# sgd710_pic32_sch.net
KiCad netlist of a schematic drawn in EAGLE
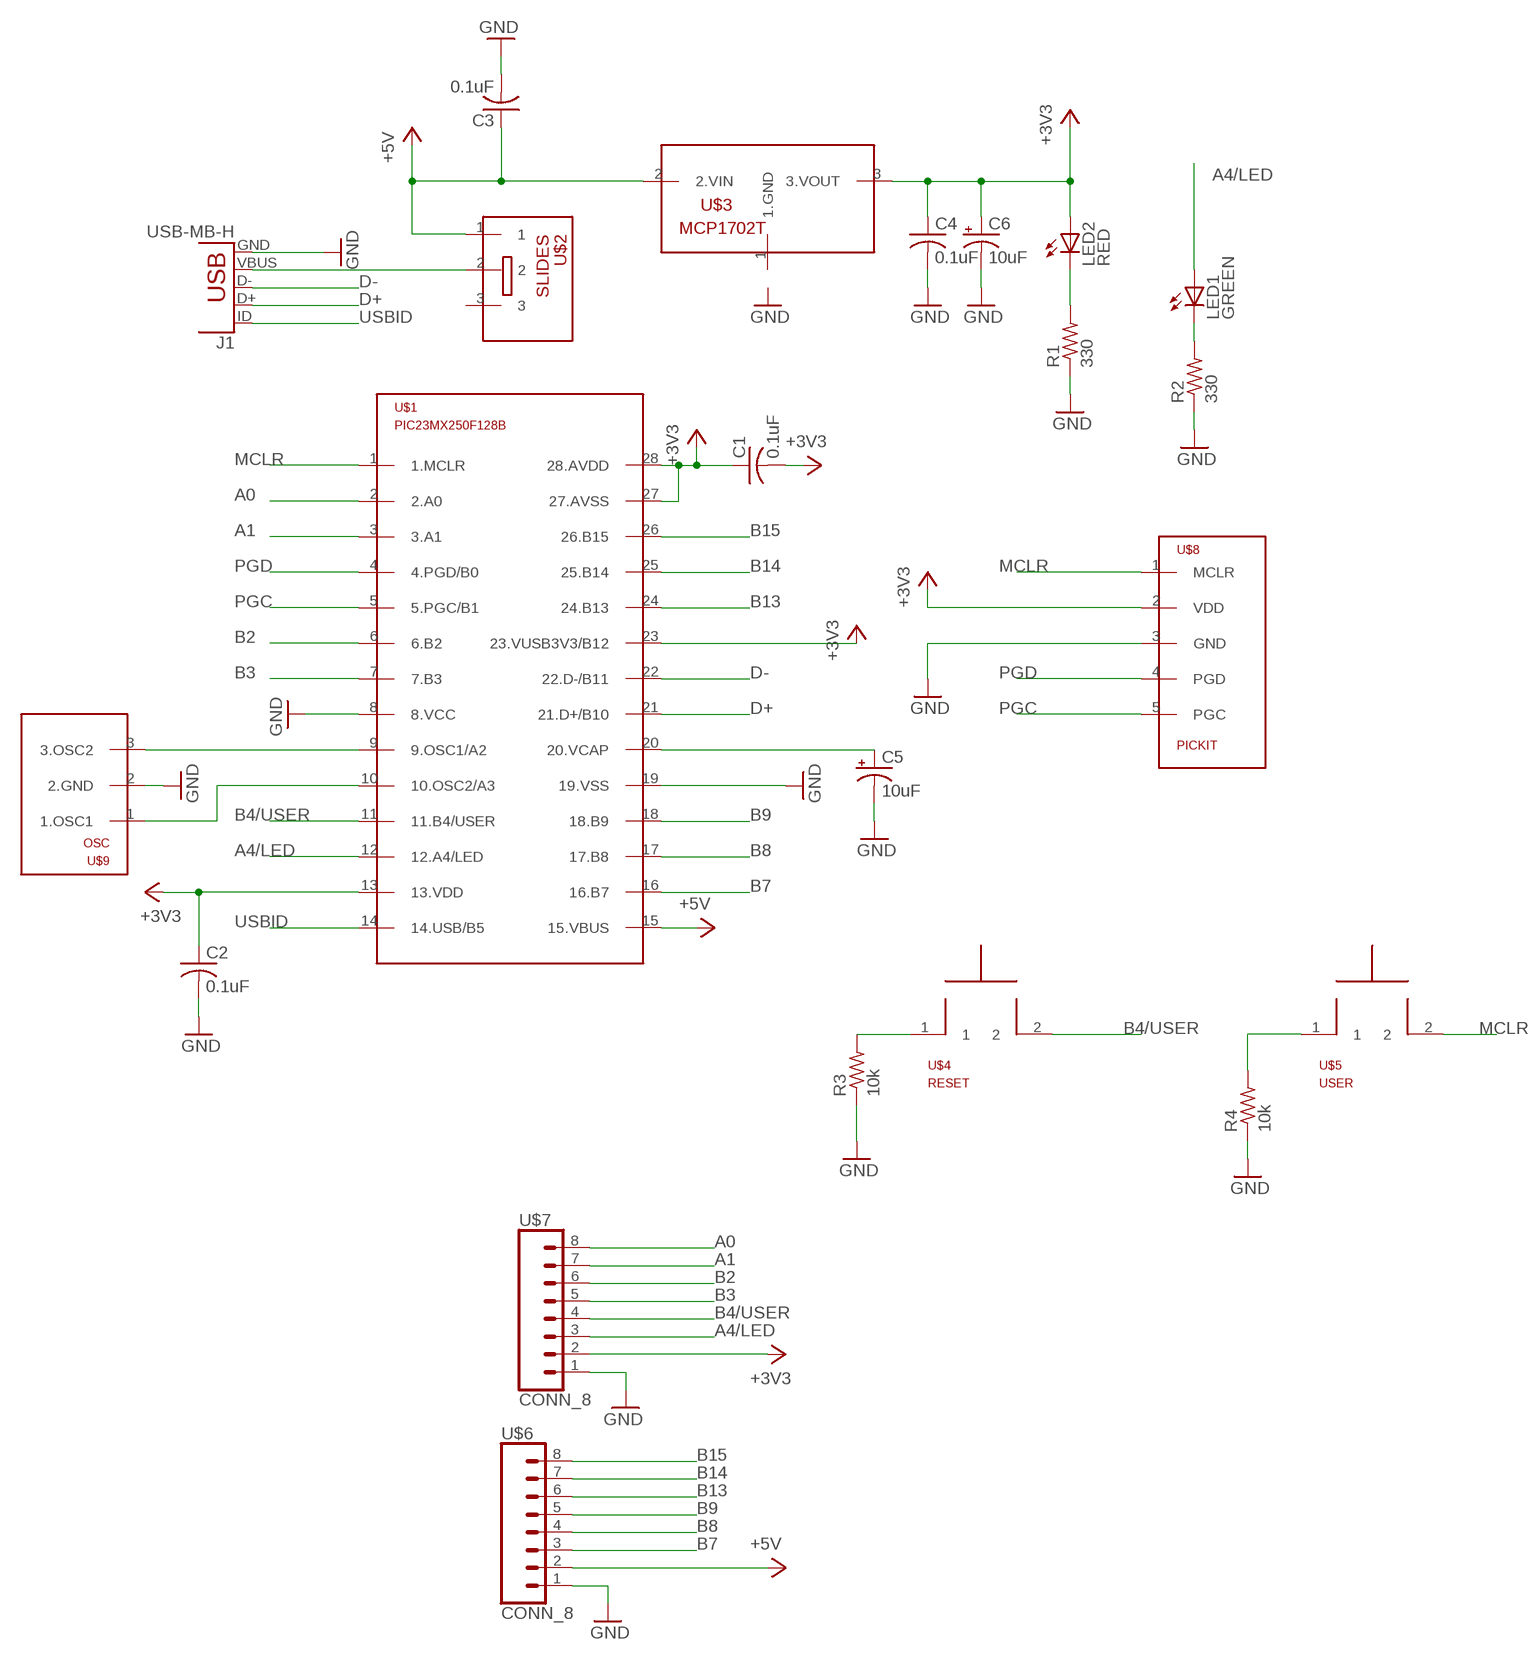
[diagram p0: schematic, sheet 1]

(export (version "E")
  (design (tool "Eeschema 10.0.6"))
  (components
    (comp (ref "C1")
      (value "0.1uF")
      (footprint "eagle-import:C025-025X050")
      (libsource (lib "eagle-import") (part "C-US025-025X050"))
    )
    (comp (ref "C2")
      (value "0.1uF")
      (footprint "eagle-import:C025-025X050")
      (libsource (lib "eagle-import") (part "C-US025-025X050"))
    )
    (comp (ref "C3")
      (value "0.1uF")
      (footprint "eagle-import:C025-025X050")
      (libsource (lib "eagle-import") (part "C-US025-025X050"))
    )
    (comp (ref "C4")
      (value "0.1uF")
      (footprint "eagle-import:C025-025X050")
      (libsource (lib "eagle-import") (part "C-US025-025X050"))
    )
    (comp (ref "C5")
      (value "10uF")
      (footprint "eagle-import:B45181A")
      (libsource (lib "eagle-import") (part "CPOL-USB45181A"))
    )
    (comp (ref "C6")
      (value "10uF")
      (footprint "eagle-import:B45181A")
      (libsource (lib "eagle-import") (part "CPOL-USB45181A"))
    )
    (comp (ref "J1")
      (value "USB-MB-H")
      (footprint "eagle-import:USB-MB-H")
      (libsource (lib "eagle-import") (part "USB-MB-H"))
    )
    (comp (ref "LED1")
      (value "GREEN")
      (footprint "eagle-import:LED3MM")
      (libsource (lib "eagle-import") (part "LED3MM"))
    )
    (comp (ref "LED2")
      (value "RED")
      (footprint "eagle-import:LED3MM")
      (libsource (lib "eagle-import") (part "LED3MM"))
    )
    (comp (ref "R1")
      (value "330")
      (footprint "eagle-import:0207_10")
      (libsource (lib "eagle-import") (part "R-US_0207/10"))
    )
    (comp (ref "R2")
      (value "330")
      (footprint "eagle-import:0207_10")
      (libsource (lib "eagle-import") (part "R-US_0207/10"))
    )
    (comp (ref "R3")
      (value "10k")
      (footprint "eagle-import:0207_10")
      (libsource (lib "eagle-import") (part "R-US_0207/10"))
    )
    (comp (ref "R4")
      (value "10k")
      (footprint "eagle-import:0207_10")
      (libsource (lib "eagle-import") (part "R-US_0207/10"))
    )
    (comp (ref "U$1")
      (value "PIC23MX250F128B")
      (footprint "eagle-import:DIL28-3")
      (libsource (lib "eagle-import") (part "PIC23MX250F128B"))
    )
    (comp (ref "U$2")
      (value "SLIDES")
      (footprint "eagle-import:SLIDE")
      (libsource (lib "eagle-import") (part "SLIDES"))
    )
    (comp (ref "U$3")
      (value "MCP1702T")
      (footprint "eagle-import:TO92")
      (libsource (lib "eagle-import") (part "MCP1702T"))
    )
    (comp (ref "U$4")
      (value "RESET")
      (footprint "eagle-import:PB")
      (libsource (lib "eagle-import") (part "PB"))
    )
    (comp (ref "U$5")
      (value "USER")
      (footprint "eagle-import:PB")
      (libsource (lib "eagle-import") (part "PB"))
    )
    (comp (ref "U$6")
      (value "CONN_8")
      (footprint "eagle-import:1X08")
      (libsource (lib "eagle-import") (part "CONN_8"))
    )
    (comp (ref "U$7")
      (value "CONN_8")
      (footprint "eagle-import:1X08")
      (libsource (lib "eagle-import") (part "CONN_8"))
    )
    (comp (ref "U$8")
      (value "PICKIT")
      (footprint "eagle-import:1X05")
      (libsource (lib "eagle-import") (part "PICKIT"))
    )
    (comp (ref "U$9")
      (value "OSC")
      (footprint "eagle-import:OSC")
      (libsource (lib "eagle-import") (part "OSC"))
    )
  )
  (nets
    (net (code "1") (name "+3V3") (class "Default")
      (node (ref "C1") (pin "1") (pinfunction "1_1") (pintype "passive"))
      (node (ref "C1") (pin "2") (pinfunction "2_2") (pintype "passive"))
      (node (ref "C2") (pin "1") (pinfunction "1_1") (pintype "passive"))
      (node (ref "C4") (pin "1") (pinfunction "1_1") (pintype "passive"))
      (node (ref "C6") (pin "+") (pinfunction "+_+") (pintype "passive"))
      (node (ref "LED2") (pin "A") (pinfunction "A_A") (pintype "passive"))
      (node (ref "U$1") (pin "13") (pinfunction "13.VDD_13") (pintype "bidirectional"))
      (node (ref "U$1") (pin "23") (pinfunction "23.VUSB3V3/B12_23") (pintype "bidirectional"))
      (node (ref "U$1") (pin "27") (pinfunction "27.AVSS_27") (pintype "bidirectional"))
      (node (ref "U$1") (pin "28") (pinfunction "28.AVDD_28") (pintype "bidirectional"))
      (node (ref "U$3") (pin "3") (pinfunction "3.VOUT_3") (pintype "bidirectional"))
      (node (ref "U$7") (pin "2") (pinfunction "2_2") (pintype "passive"))
      (node (ref "U$8") (pin "2") (pinfunction "VDD_2") (pintype "bidirectional"))
    )
    (net (code "2") (name "+5V") (class "Default")
      (node (ref "C3") (pin "1") (pinfunction "1_1") (pintype "passive"))
      (node (ref "U$1") (pin "15") (pinfunction "15.VBUS_15") (pintype "bidirectional"))
      (node (ref "U$2") (pin "1") (pinfunction "1_1") (pintype "bidirectional"))
      (node (ref "U$3") (pin "2") (pinfunction "2.VIN_2") (pintype "bidirectional"))
      (node (ref "U$6") (pin "2") (pinfunction "2_2") (pintype "passive"))
    )
    (net (code "3") (name "/A0") (class "Default")
      (node (ref "U$1") (pin "2") (pinfunction "2.A0_2") (pintype "bidirectional"))
      (node (ref "U$7") (pin "8") (pinfunction "8_8") (pintype "passive"))
    )
    (net (code "4") (name "/A1") (class "Default")
      (node (ref "U$1") (pin "3") (pinfunction "3.A1_3") (pintype "bidirectional"))
      (node (ref "U$7") (pin "7") (pinfunction "7_7") (pintype "passive"))
    )
    (net (code "5") (name "/A4{slash}LED") (class "Default")
      (node (ref "LED1") (pin "A") (pinfunction "A_A") (pintype "passive"))
      (node (ref "U$1") (pin "12") (pinfunction "12.A4/LED_12") (pintype "bidirectional"))
      (node (ref "U$7") (pin "3") (pinfunction "3_3") (pintype "passive"))
    )
    (net (code "6") (name "/B2") (class "Default")
      (node (ref "U$1") (pin "6") (pinfunction "6.B2_6") (pintype "bidirectional"))
      (node (ref "U$7") (pin "6") (pinfunction "6_6") (pintype "passive"))
    )
    (net (code "7") (name "/B3") (class "Default")
      (node (ref "U$1") (pin "7") (pinfunction "7.B3_7") (pintype "bidirectional"))
      (node (ref "U$7") (pin "5") (pinfunction "5_5") (pintype "passive"))
    )
    (net (code "8") (name "/B4{slash}USER") (class "Default")
      (node (ref "U$1") (pin "11") (pinfunction "11.B4/USER_11") (pintype "bidirectional"))
      (node (ref "U$4") (pin "2") (pinfunction "2_2") (pintype "bidirectional"))
      (node (ref "U$7") (pin "4") (pinfunction "4_4") (pintype "passive"))
    )
    (net (code "9") (name "/B7") (class "Default")
      (node (ref "U$1") (pin "16") (pinfunction "16.B7_16") (pintype "bidirectional"))
      (node (ref "U$6") (pin "3") (pinfunction "3_3") (pintype "passive"))
    )
    (net (code "10") (name "/B8") (class "Default")
      (node (ref "U$1") (pin "17") (pinfunction "17.B8_17") (pintype "bidirectional"))
      (node (ref "U$6") (pin "4") (pinfunction "4_4") (pintype "passive"))
    )
    (net (code "11") (name "/B9") (class "Default")
      (node (ref "U$1") (pin "18") (pinfunction "18.B9_18") (pintype "bidirectional"))
      (node (ref "U$6") (pin "5") (pinfunction "5_5") (pintype "passive"))
    )
    (net (code "12") (name "/B13") (class "Default")
      (node (ref "U$1") (pin "24") (pinfunction "24.B13_24") (pintype "bidirectional"))
      (node (ref "U$6") (pin "6") (pinfunction "6_6") (pintype "passive"))
    )
    (net (code "13") (name "/B14") (class "Default")
      (node (ref "U$1") (pin "25") (pinfunction "25.B14_25") (pintype "bidirectional"))
      (node (ref "U$6") (pin "7") (pinfunction "7_7") (pintype "passive"))
    )
    (net (code "14") (name "/B15") (class "Default")
      (node (ref "U$1") (pin "26") (pinfunction "26.B15_26") (pintype "bidirectional"))
      (node (ref "U$6") (pin "8") (pinfunction "8_8") (pintype "passive"))
    )
    (net (code "15") (name "/D+") (class "Default")
      (node (ref "J1") (pin "D+") (pinfunction "D+_D+") (pintype "bidirectional"))
      (node (ref "U$1") (pin "21") (pinfunction "21.D+/B10_21") (pintype "bidirectional"))
    )
    (net (code "16") (name "/D-") (class "Default")
      (node (ref "J1") (pin "D-") (pinfunction "D-_D-") (pintype "bidirectional"))
      (node (ref "U$1") (pin "22") (pinfunction "22.D-/B11_22") (pintype "bidirectional"))
    )
    (net (code "17") (name "/MCLR") (class "Default")
      (node (ref "U$1") (pin "1") (pinfunction "1.MCLR_1") (pintype "bidirectional"))
      (node (ref "U$5") (pin "2") (pinfunction "2_2") (pintype "bidirectional"))
      (node (ref "U$8") (pin "1") (pinfunction "MCLR_1") (pintype "bidirectional"))
    )
    (net (code "18") (name "/PGC") (class "Default")
      (node (ref "U$1") (pin "5") (pinfunction "5.PGC/B1_5") (pintype "bidirectional"))
      (node (ref "U$8") (pin "5") (pinfunction "PGC_5") (pintype "bidirectional"))
    )
    (net (code "19") (name "/PGD") (class "Default")
      (node (ref "U$1") (pin "4") (pinfunction "4.PGD/B0_4") (pintype "bidirectional"))
      (node (ref "U$8") (pin "4") (pinfunction "PGD_4") (pintype "bidirectional"))
    )
    (net (code "20") (name "/USBID") (class "Default")
      (node (ref "J1") (pin "ID") (pinfunction "ID_ID") (pintype "bidirectional"))
      (node (ref "U$1") (pin "14") (pinfunction "14.USB/B5_14") (pintype "bidirectional"))
    )
    (net (code "21") (name "GND") (class "Default")
      (node (ref "C2") (pin "2") (pinfunction "2_2") (pintype "passive"))
      (node (ref "C3") (pin "2") (pinfunction "2_2") (pintype "passive"))
      (node (ref "C4") (pin "2") (pinfunction "2_2") (pintype "passive"))
      (node (ref "C5") (pin "-") (pinfunction "-_-") (pintype "passive"))
      (node (ref "C6") (pin "-") (pinfunction "-_-") (pintype "passive"))
      (node (ref "J1") (pin "GND") (pinfunction "GND_GND") (pintype "bidirectional"))
      (node (ref "R1") (pin "1") (pinfunction "1_1") (pintype "passive"))
      (node (ref "R2") (pin "1") (pinfunction "1_1") (pintype "passive"))
      (node (ref "R3") (pin "1") (pinfunction "1_1") (pintype "passive"))
      (node (ref "R4") (pin "1") (pinfunction "1_1") (pintype "passive"))
      (node (ref "U$1") (pin "19") (pinfunction "19.VSS_19") (pintype "bidirectional"))
      (node (ref "U$1") (pin "8") (pinfunction "8.VCC_8") (pintype "bidirectional"))
      (node (ref "U$6") (pin "1") (pinfunction "1_1") (pintype "passive"))
      (node (ref "U$7") (pin "1") (pinfunction "1_1") (pintype "passive"))
      (node (ref "U$8") (pin "3") (pinfunction "GND_3") (pintype "bidirectional"))
      (node (ref "U$9") (pin "2") (pinfunction "2.GND_2") (pintype "bidirectional"))
    )
    (net (code "22") (name "Net-(J1-PadVBUS)") (class "Default")
      (node (ref "J1") (pin "VBUS") (pinfunction "VBUS_VBUS") (pintype "bidirectional"))
      (node (ref "U$2") (pin "2") (pinfunction "2_2") (pintype "bidirectional"))
    )
    (net (code "23") (name "Net-(LED1-C)") (class "Default")
      (node (ref "LED1") (pin "K") (pinfunction "C_K") (pintype "passive"))
      (node (ref "R2") (pin "2") (pinfunction "2_2") (pintype "passive"))
    )
    (net (code "24") (name "Net-(LED2-C)") (class "Default")
      (node (ref "LED2") (pin "K") (pinfunction "C_K") (pintype "passive"))
      (node (ref "R1") (pin "2") (pinfunction "2_2") (pintype "passive"))
    )
    (net (code "25") (name "Net-(R3-Pad2)") (class "Default")
      (node (ref "R3") (pin "2") (pinfunction "2_2") (pintype "passive"))
      (node (ref "U$4") (pin "1") (pinfunction "1_1") (pintype "bidirectional"))
    )
    (net (code "26") (name "Net-(R4-Pad2)") (class "Default")
      (node (ref "R4") (pin "2") (pinfunction "2_2") (pintype "passive"))
      (node (ref "U$5") (pin "1") (pinfunction "1_1") (pintype "bidirectional"))
    )
    (net (code "27") (name "Net-(U$1-9.OSC1{slash}A2)") (class "Default")
      (node (ref "U$1") (pin "9") (pinfunction "9.OSC1/A2_9") (pintype "bidirectional"))
      (node (ref "U$9") (pin "3") (pinfunction "3.OSC2_3") (pintype "bidirectional"))
    )
    (net (code "28") (name "Net-(U$1-10.OSC2{slash}A3)") (class "Default")
      (node (ref "U$1") (pin "10") (pinfunction "10.OSC2/A3_10") (pintype "bidirectional"))
      (node (ref "U$9") (pin "1") (pinfunction "1.OSC1_1") (pintype "bidirectional"))
    )
    (net (code "29") (name "Net-(U$1-20.VCAP)") (class "Default")
      (node (ref "C5") (pin "+") (pinfunction "+_+") (pintype "passive"))
      (node (ref "U$1") (pin "20") (pinfunction "20.VCAP_20") (pintype "bidirectional"))
    )
    (net (code "30") (name "unconnected-(U$2-Pad3)") (class "Default")
      (node (ref "U$2") (pin "3") (pinfunction "3_3") (pintype "bidirectional"))
    )
    (net (code "31") (name "unconnected-(U$3-1.GND-Pad1)") (class "Default")
      (node (ref "U$3") (pin "1") (pinfunction "1.GND_1") (pintype "bidirectional"))
    )
  )
)
